# BW1097_Connector.net
KiCad netlist of a schematic drawn in Altium Designer
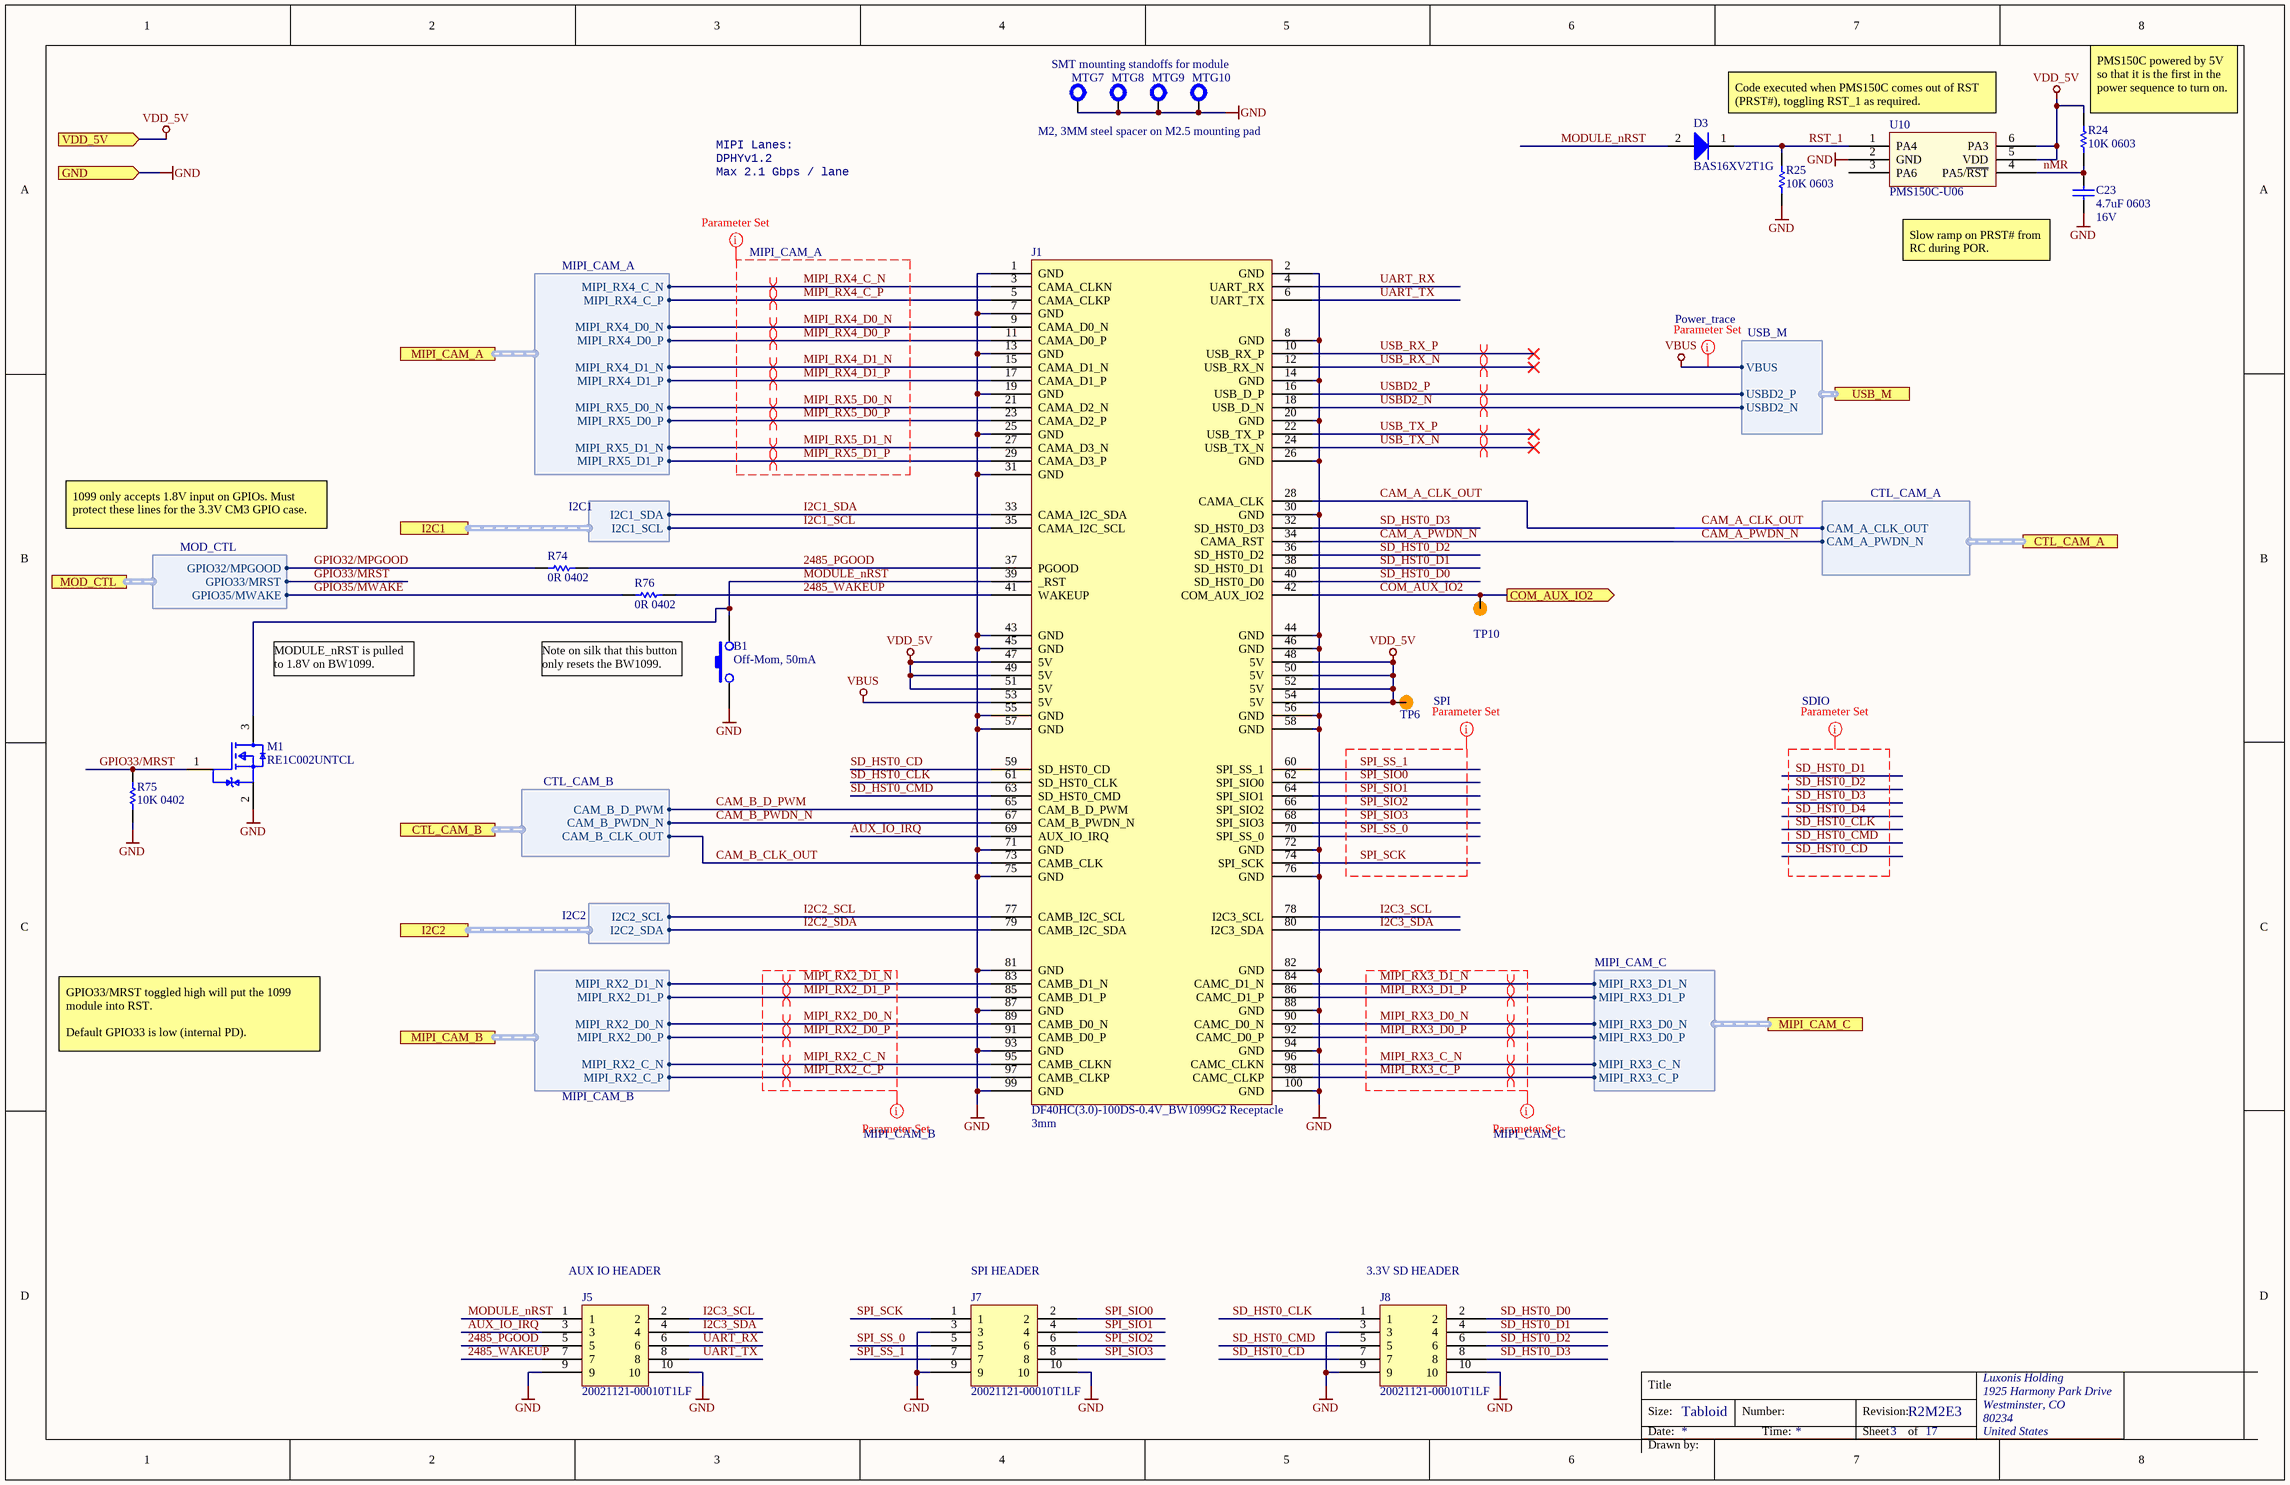
[diagram p0: BW1097_Connector.SchDoc]

(export (version "E")
  (design (tool "Eeschema 10.0.6"))
  (components
    (comp (ref "B1")
      (value "Off-Mom, 50mA")
      (footprint "LuxonisMaster:DTSM-32N-V")
      (description "SWITCH TACTILE SMT 3.5mm * 6mm , brown 160gf")
      (libsource (lib "LuxonisMaster") (part "DTSM-32N-V"))
    )
    (comp (ref "C23")
      (value "4.7uF 0603")
      (footprint "CAP_Altium_Vault_Generic:CAPC0603(1608)100_N")
      (description "CAP CER 4.7UF 16V X5R 0603 10%")
      (fields (field (name "TOLERANCE") "10%") (field (name "VOLTAGE RATING") "16V"))
      (libsource (lib "LuxonisMaster") (part "GRM188R61C475KAAJD"))
    )
    (comp (ref "D3")
      (value "BAS16XV2T1G")
      (footprint "LuxonisMaster:BAS16XV2T1G")
      (description "DIODE GEN PURP 75V 200MA SOD523")
      (libsource (lib "LuxonisMaster") (part "BAS16XV2T1G"))
    )
    (comp (ref "J1")
      (value "DF40HC(3.0)-100DS-0.4V_BW1099G2 Receptacle")
      (footprint "LuxonisMaster:DF40HC-3.0-100DS-0.4V_minpad")
      (description "CONN RCPT 100POS 0.4MM SMD GOLD")
      (fields (field (name "MATED STACKING HEIGHT") "3mm"))
      (libsource (lib "LuxonisMaster") (part "DF40HC(3.0)-100DS-0.4V_BW1099_G2"))
    )
    (comp (ref "J5")
      (value "20021121-00010T1LF")
      (footprint "LuxonisMaster:20021121-00010T1LF")
      (description "CONN HEADER SMD 10POS 1.27MM")
      (libsource (lib "LuxonisMaster") (part "20021121-00010T1LF"))
    )
    (comp (ref "J7")
      (value "20021121-00010T1LF")
      (footprint "LuxonisMaster:20021121-00010T1LF")
      (description "CONN HEADER SMD 10POS 1.27MM")
      (libsource (lib "LuxonisMaster") (part "20021121-00010T1LF"))
    )
    (comp (ref "J8")
      (value "20021121-00010T1LF")
      (footprint "LuxonisMaster:20021121-00010T1LF")
      (description "CONN HEADER SMD 10POS 1.27MM")
      (libsource (lib "LuxonisMaster") (part "20021121-00010T1LF"))
    )
    (comp (ref "M1")
      (value "RE1C002UNTCL")
      (footprint "LuxonisMaster:RE1C002UNTCL")
      (description "MOSFET N-CH 20V 0.2A EMT3")
      (libsource (lib "LuxonisMaster") (part "RE1C002UNTCL"))
    )
    (comp (ref "MTG7")
      (value "M2, 3MM steel spacer on M2.5 mounting pad")
      (footprint "LuxonisMaster:9774030243R")
      (description "MP ROUND STANDOFF M2X0.4 STEEL 3MM")
      (libsource (lib "LuxonisMaster") (part "9774030243R"))
    )
    (comp (ref "MTG8")
      (value "M2, 3MM steel spacer on M2.5 mounting pad")
      (footprint "LuxonisMaster:9774030243R")
      (description "MP ROUND STANDOFF M2X0.4 STEEL 3MM")
      (libsource (lib "LuxonisMaster") (part "9774030243R"))
    )
    (comp (ref "MTG9")
      (value "M2, 3MM steel spacer on M2.5 mounting pad")
      (footprint "LuxonisMaster:9774030243R")
      (description "MP ROUND STANDOFF M2X0.4 STEEL 3MM")
      (libsource (lib "LuxonisMaster") (part "9774030243R"))
    )
    (comp (ref "MTG10")
      (value "M2, 3MM steel spacer on M2.5 mounting pad")
      (footprint "LuxonisMaster:9774030243R")
      (description "MP ROUND STANDOFF M2X0.4 STEEL 3MM")
      (libsource (lib "LuxonisMaster") (part "9774030243R"))
    )
    (comp (ref "R24")
      (value "10K 0603")
      (footprint "RES_Altium_Vault_Generic:RESC0603(1608)_N")
      (description "RES SMD 10K OHM 1% 1/10W 0603")
      (fields (field (name "TOLERANCE") "1%"))
      (libsource (lib "LuxonisMaster") (part "RC0603FR-0710KL"))
    )
    (comp (ref "R25")
      (value "10K 0603")
      (footprint "RES_Altium_Vault_Generic:RESC0603(1608)_N")
      (description "RES SMD 10K OHM 1% 1/10W 0603")
      (fields (field (name "TOLERANCE") "1%"))
      (libsource (lib "LuxonisMaster") (part "RC0603FR-0710KL"))
    )
    (comp (ref "R74")
      (value "0R 0402")
      (footprint "RES_Altium_Vault_Generic:RESC0402(1005)_N")
      (description "RES SMD 0 OHM JUMPER 1/16W 0402")
      (fields (field (name "TOLERANCE") "5%"))
      (libsource (lib "LuxonisMaster") (part "CRCW04020000Z0ED"))
    )
    (comp (ref "R75")
      (value "10K 0402")
      (footprint "RES_Altium_Vault_Generic:RESC0402(1005)_N")
      (fields (field (name "TOLERANCE") "1%"))
      (libsource (lib "LuxonisMaster") (part "RC0402FR-1310KL"))
    )
    (comp (ref "R76")
      (value "0R 0402")
      (footprint "RES_Altium_Vault_Generic:RESC0402(1005)_N")
      (description "RES SMD 0 OHM JUMPER 1/16W 0402")
      (fields (field (name "TOLERANCE") "5%"))
      (libsource (lib "LuxonisMaster") (part "CRCW04020000Z0ED"))
    )
    (comp (ref "TP6")
      (value "TP100_200_NS")
      (footprint "LuxonisMaster:TP100_200_NS")
      (libsource (lib "LuxonisMaster") (part "TEST_POINT"))
    )
    (comp (ref "TP10")
      (value "TP100_200_NS")
      (footprint "LuxonisMaster:TP100_200_NS")
      (libsource (lib "LuxonisMaster") (part "TEST_POINT"))
    )
    (comp (ref "U10")
      (value "PMS150C-U06")
      (footprint "LuxonisMaster:PMS150C-U06")
      (description "Padauk 8bit OTP Type IO Controller - (SOT-23-6)")
      (libsource (lib "LuxonisMaster") (part "PMS150C-U06"))
    )
  )
  (nets
    (net (code "10") (name "/2485_PGOOD") (class "Default")
      (node (ref "J1") (pin "37") (pinfunction "PGOOD_37") (pintype "passive"))
      (node (ref "J5") (pin "5") (pinfunction "5_5") (pintype "passive"))
      (node (ref "R74") (pin "1") (pinfunction "1_1") (pintype "passive"))
    )
    (net (code "11") (name "/2485_WAKEUP") (class "Default")
      (node (ref "J1") (pin "41") (pinfunction "WAKEUP_41") (pintype "passive"))
      (node (ref "J5") (pin "7") (pinfunction "7_7") (pintype "passive"))
      (node (ref "R76") (pin "1") (pinfunction "1_1") (pintype "passive"))
    )
    (net (code "12") (name "/AUX_IO_IRQ") (class "Default")
      (node (ref "J1") (pin "69") (pinfunction "AUX_IO_IRQ_69") (pintype "passive"))
      (node (ref "J5") (pin "3") (pinfunction "3_3") (pintype "passive"))
    )
    (net (code "13") (name "/CAM_A_CLK_OUT") (class "Default")
      (node (ref "J1") (pin "28") (pinfunction "CAMA_CLK_28") (pintype "passive"))
    )
    (net (code "14") (name "/CAM_A_PWDN_N") (class "Default")
      (node (ref "J1") (pin "34") (pinfunction "CAMA_RST_34") (pintype "passive"))
    )
    (net (code "15") (name "/CAM_B_CLK_OUT") (class "Default")
      (node (ref "J1") (pin "73") (pinfunction "CAMB_CLK_73") (pintype "passive"))
    )
    (net (code "16") (name "/CAM_B_D_PWM") (class "Default")
      (node (ref "J1") (pin "65") (pinfunction "CAM_B_D_PWM_65") (pintype "passive"))
    )
    (net (code "17") (name "/CAM_B_PWDN_N") (class "Default")
      (node (ref "J1") (pin "67") (pinfunction "CAM_B_PWDN_N_67") (pintype "passive"))
    )
    (net (code "18") (name "/COM_AUX_IO2") (class "Default")
      (node (ref "J1") (pin "42") (pinfunction "COM_AUX_IO2_42") (pintype "passive"))
      (node (ref "TP10") (pin "1") (pintype "passive"))
    )
    (net (code "19") (name "/GPIO32{slash}MPGOOD") (class "Default")
      (node (ref "R74") (pin "2") (pinfunction "2_2") (pintype "passive"))
    )
    (net (code "20") (name "/GPIO33{slash}MRST") (class "Default")
      (node (ref "M1") (pin "1") (pinfunction "Gate_1") (pintype "passive"))
      (node (ref "R75") (pin "2") (pinfunction "2_2") (pintype "passive"))
    )
    (net (code "21") (name "/GPIO35{slash}MWAKE") (class "Default")
      (node (ref "R76") (pin "2") (pinfunction "2_2") (pintype "passive"))
    )
    (net (code "22") (name "/I2C1_SCL") (class "Default")
      (node (ref "J1") (pin "35") (pinfunction "CAMA_I2C_SCL_35") (pintype "passive"))
    )
    (net (code "23") (name "/I2C1_SDA") (class "Default")
      (node (ref "J1") (pin "33") (pinfunction "CAMA_I2C_SDA_33") (pintype "passive"))
    )
    (net (code "24") (name "/I2C2_SCL") (class "Default")
      (node (ref "J1") (pin "77") (pinfunction "CAMB_I2C_SCL_77") (pintype "passive"))
    )
    (net (code "25") (name "/I2C2_SDA") (class "Default")
      (node (ref "J1") (pin "79") (pinfunction "CAMB_I2C_SDA_79") (pintype "passive"))
    )
    (net (code "26") (name "/I2C3_SCL") (class "Default")
      (node (ref "J1") (pin "78") (pinfunction "I2C3_SCL_78") (pintype "passive"))
      (node (ref "J5") (pin "2") (pinfunction "2_2") (pintype "passive"))
    )
    (net (code "27") (name "/I2C3_SDA") (class "Default")
      (node (ref "J1") (pin "80") (pinfunction "I2C3_SDA_80") (pintype "passive"))
      (node (ref "J5") (pin "4") (pinfunction "4_4") (pintype "passive"))
    )
    (net (code "28") (name "/MIPI_RX2_C_N") (class "Default")
      (node (ref "J1") (pin "95") (pinfunction "CAMB_CLKN_95") (pintype "passive"))
    )
    (net (code "29") (name "/MIPI_RX2_C_P") (class "Default")
      (node (ref "J1") (pin "97") (pinfunction "CAMB_CLKP_97") (pintype "passive"))
    )
    (net (code "30") (name "/MIPI_RX2_D0_N") (class "Default")
      (node (ref "J1") (pin "89") (pinfunction "CAMB_D0_N_89") (pintype "passive"))
    )
    (net (code "31") (name "/MIPI_RX2_D0_P") (class "Default")
      (node (ref "J1") (pin "91") (pinfunction "CAMB_D0_P_91") (pintype "passive"))
    )
    (net (code "32") (name "/MIPI_RX2_D1_N") (class "Default")
      (node (ref "J1") (pin "83") (pinfunction "CAMB_D1_N_83") (pintype "passive"))
    )
    (net (code "33") (name "/MIPI_RX2_D1_P") (class "Default")
      (node (ref "J1") (pin "85") (pinfunction "CAMB_D1_P_85") (pintype "passive"))
    )
    (net (code "34") (name "/MIPI_RX3_C_N") (class "Default")
      (node (ref "J1") (pin "96") (pinfunction "CAMC_CLKN_96") (pintype "passive"))
    )
    (net (code "35") (name "/MIPI_RX3_C_P") (class "Default")
      (node (ref "J1") (pin "98") (pinfunction "CAMC_CLKP_98") (pintype "passive"))
    )
    (net (code "36") (name "/MIPI_RX3_D0_N") (class "Default")
      (node (ref "J1") (pin "90") (pinfunction "CAMC_D0_N_90") (pintype "passive"))
    )
    (net (code "37") (name "/MIPI_RX3_D0_P") (class "Default")
      (node (ref "J1") (pin "92") (pinfunction "CAMC_D0_P_92") (pintype "passive"))
    )
    (net (code "38") (name "/MIPI_RX3_D1_N") (class "Default")
      (node (ref "J1") (pin "84") (pinfunction "CAMC_D1_N_84") (pintype "passive"))
    )
    (net (code "39") (name "/MIPI_RX3_D1_P") (class "Default")
      (node (ref "J1") (pin "86") (pinfunction "CAMC_D1_P_86") (pintype "passive"))
    )
    (net (code "40") (name "/MIPI_RX4_C_N") (class "Default")
      (node (ref "J1") (pin "3") (pinfunction "CAMA_CLKN_3") (pintype "passive"))
    )
    (net (code "41") (name "/MIPI_RX4_C_P") (class "Default")
      (node (ref "J1") (pin "5") (pinfunction "CAMA_CLKP_5") (pintype "passive"))
    )
    (net (code "42") (name "/MIPI_RX4_D0_N") (class "Default")
      (node (ref "J1") (pin "9") (pinfunction "CAMA_D0_N_9") (pintype "passive"))
    )
    (net (code "43") (name "/MIPI_RX4_D0_P") (class "Default")
      (node (ref "J1") (pin "11") (pinfunction "CAMA_D0_P_11") (pintype "passive"))
    )
    (net (code "44") (name "/MIPI_RX4_D1_N") (class "Default")
      (node (ref "J1") (pin "15") (pinfunction "CAMA_D1_N_15") (pintype "passive"))
    )
    (net (code "45") (name "/MIPI_RX4_D1_P") (class "Default")
      (node (ref "J1") (pin "17") (pinfunction "CAMA_D1_P_17") (pintype "passive"))
    )
    (net (code "46") (name "/MIPI_RX5_D0_N") (class "Default")
      (node (ref "J1") (pin "21") (pinfunction "CAMA_D2_N_21") (pintype "passive"))
    )
    (net (code "47") (name "/MIPI_RX5_D0_P") (class "Default")
      (node (ref "J1") (pin "23") (pinfunction "CAMA_D2_P_23") (pintype "passive"))
    )
    (net (code "48") (name "/MIPI_RX5_D1_N") (class "Default")
      (node (ref "J1") (pin "27") (pinfunction "CAMA_D3_N_27") (pintype "passive"))
    )
    (net (code "49") (name "/MIPI_RX5_D1_P") (class "Default")
      (node (ref "J1") (pin "29") (pinfunction "CAMA_D3_P_29") (pintype "passive"))
    )
    (net (code "50") (name "/MODULE_nRST") (class "Default")
      (node (ref "B1") (pin "2") (pinfunction "2_2") (pintype "passive"))
      (node (ref "D3") (pin "2") (pinfunction "A_2") (pintype "passive"))
      (node (ref "J1") (pin "39") (pinfunction "_RST_39") (pintype "passive"))
      (node (ref "J5") (pin "1") (pinfunction "1_1") (pintype "passive"))
      (node (ref "M1") (pin "3") (pinfunction "Drain_3") (pintype "passive"))
    )
    (net (code "51") (name "/RST_1") (class "Default")
      (node (ref "D3") (pin "1") (pinfunction "K_1") (pintype "passive"))
      (node (ref "R25") (pin "2") (pinfunction "2_2") (pintype "passive"))
      (node (ref "U10") (pin "1") (pinfunction "PA4_1") (pintype "passive"))
    )
    (net (code "52") (name "/SD_HST0_CD") (class "Default")
      (node (ref "J1") (pin "59") (pinfunction "SD_HST0_CD_59") (pintype "passive"))
      (node (ref "J8") (pin "7") (pinfunction "7_7") (pintype "passive"))
    )
    (net (code "53") (name "/SD_HST0_CLK") (class "Default")
      (node (ref "J1") (pin "61") (pinfunction "SD_HST0_CLK_61") (pintype "passive"))
      (node (ref "J8") (pin "1") (pinfunction "1_1") (pintype "passive"))
    )
    (net (code "54") (name "/SD_HST0_CMD") (class "Default")
      (node (ref "J1") (pin "63") (pinfunction "SD_HST0_CMD_63") (pintype "passive"))
      (node (ref "J8") (pin "5") (pinfunction "5_5") (pintype "passive"))
    )
    (net (code "55") (name "/SD_HST0_D0") (class "Default")
      (node (ref "J1") (pin "40") (pinfunction "SD_HST0_D0_40") (pintype "passive"))
      (node (ref "J8") (pin "2") (pinfunction "2_2") (pintype "passive"))
    )
    (net (code "56") (name "/SD_HST0_D1") (class "Default")
      (node (ref "J1") (pin "38") (pinfunction "SD_HST0_D1_38") (pintype "passive"))
      (node (ref "J8") (pin "4") (pinfunction "4_4") (pintype "passive"))
    )
    (net (code "57") (name "/SD_HST0_D2") (class "Default")
      (node (ref "J1") (pin "36") (pinfunction "SD_HST0_D2_36") (pintype "passive"))
      (node (ref "J8") (pin "6") (pinfunction "6_6") (pintype "passive"))
    )
    (net (code "58") (name "/SD_HST0_D3") (class "Default")
      (node (ref "J1") (pin "32") (pinfunction "SD_HST0_D3_32") (pintype "passive"))
      (node (ref "J8") (pin "8") (pinfunction "8_8") (pintype "passive"))
    )
    (net (code "60") (name "/SPI_SCK") (class "Default")
      (node (ref "J1") (pin "74") (pinfunction "SPI_SCK_74") (pintype "passive"))
      (node (ref "J7") (pin "1") (pinfunction "1_1") (pintype "passive"))
    )
    (net (code "61") (name "/SPI_SIO0") (class "Default")
      (node (ref "J1") (pin "62") (pinfunction "SPI_SIO0_62") (pintype "passive"))
      (node (ref "J7") (pin "2") (pinfunction "2_2") (pintype "passive"))
    )
    (net (code "62") (name "/SPI_SIO1") (class "Default")
      (node (ref "J1") (pin "64") (pinfunction "SPI_SIO1_64") (pintype "passive"))
      (node (ref "J7") (pin "4") (pinfunction "4_4") (pintype "passive"))
    )
    (net (code "63") (name "/SPI_SIO2") (class "Default")
      (node (ref "J1") (pin "66") (pinfunction "SPI_SIO2_66") (pintype "passive"))
      (node (ref "J7") (pin "6") (pinfunction "6_6") (pintype "passive"))
    )
    (net (code "64") (name "/SPI_SIO3") (class "Default")
      (node (ref "J1") (pin "68") (pinfunction "SPI_SIO3_68") (pintype "passive"))
      (node (ref "J7") (pin "8") (pinfunction "8_8") (pintype "passive"))
    )
    (net (code "65") (name "/SPI_SS_0") (class "Default")
      (node (ref "J1") (pin "70") (pinfunction "SPI_SS_0_70") (pintype "passive"))
      (node (ref "J7") (pin "5") (pinfunction "5_5") (pintype "passive"))
    )
    (net (code "66") (name "/SPI_SS_1") (class "Default")
      (node (ref "J1") (pin "60") (pinfunction "SPI_SS_1_60") (pintype "passive"))
      (node (ref "J7") (pin "7") (pinfunction "7_7") (pintype "passive"))
    )
    (net (code "67") (name "/UART_RX") (class "Default")
      (node (ref "J1") (pin "4") (pinfunction "UART_RX_4") (pintype "passive"))
      (node (ref "J5") (pin "6") (pinfunction "6_6") (pintype "passive"))
    )
    (net (code "68") (name "/UART_TX") (class "Default")
      (node (ref "J1") (pin "6") (pinfunction "UART_TX_6") (pintype "passive"))
      (node (ref "J5") (pin "8") (pinfunction "8_8") (pintype "passive"))
    )
    (net (code "69") (name "/USBD2_N") (class "Default")
      (node (ref "J1") (pin "18") (pinfunction "USB_D_N_18") (pintype "passive"))
    )
    (net (code "70") (name "/USBD2_P") (class "Default")
      (node (ref "J1") (pin "16") (pinfunction "USB_D_P_16") (pintype "passive"))
    )
    (net (code "71") (name "/USB_RX_N") (class "Default")
      (node (ref "J1") (pin "12") (pinfunction "USB_RX_N_12") (pintype "passive+no_connect"))
    )
    (net (code "72") (name "/USB_RX_P") (class "Default")
      (node (ref "J1") (pin "10") (pinfunction "USB_RX_P_10") (pintype "passive+no_connect"))
    )
    (net (code "73") (name "/USB_TX_N") (class "Default")
      (node (ref "J1") (pin "24") (pinfunction "USB_TX_N_24") (pintype "passive+no_connect"))
    )
    (net (code "74") (name "/USB_TX_P") (class "Default")
      (node (ref "J1") (pin "22") (pinfunction "USB_TX_P_22") (pintype "passive+no_connect"))
    )
    (net (code "75") (name "/nMR") (class "Default")
      (node (ref "C23") (pin "2") (pinfunction "2_2") (pintype "passive"))
      (node (ref "R24") (pin "1") (pinfunction "1_1") (pintype "passive"))
      (node (ref "U10") (pin "4") (pinfunction "PA5/~{RST}_4") (pintype "passive"))
    )
    (net (code "85") (name "GND") (class "Default")
      (node (ref "B1") (pin "1") (pinfunction "1_1") (pintype "passive"))
      (node (ref "C23") (pin "1") (pinfunction "1_1") (pintype "passive"))
      (node (ref "J1") (pin "1") (pinfunction "GND_1") (pintype "passive"))
      (node (ref "J1") (pin "100") (pinfunction "GND_100") (pintype "passive"))
      (node (ref "J1") (pin "13") (pinfunction "GND_13") (pintype "passive"))
      (node (ref "J1") (pin "14") (pinfunction "GND_14") (pintype "passive"))
      (node (ref "J1") (pin "19") (pinfunction "GND_19") (pintype "passive"))
      (node (ref "J1") (pin "2") (pinfunction "GND_2") (pintype "passive"))
      (node (ref "J1") (pin "20") (pinfunction "GND_20") (pintype "passive"))
      (node (ref "J1") (pin "25") (pinfunction "GND_25") (pintype "passive"))
      (node (ref "J1") (pin "26") (pinfunction "GND_26") (pintype "passive"))
      (node (ref "J1") (pin "30") (pinfunction "GND_30") (pintype "passive"))
      (node (ref "J1") (pin "31") (pinfunction "GND_31") (pintype "passive"))
      (node (ref "J1") (pin "43") (pinfunction "GND_43") (pintype "passive"))
      (node (ref "J1") (pin "44") (pinfunction "GND_44") (pintype "passive"))
      (node (ref "J1") (pin "45") (pinfunction "GND_45") (pintype "passive"))
      (node (ref "J1") (pin "46") (pinfunction "GND_46") (pintype "passive"))
      (node (ref "J1") (pin "55") (pinfunction "GND_55") (pintype "passive"))
      (node (ref "J1") (pin "56") (pinfunction "GND_56") (pintype "passive"))
      (node (ref "J1") (pin "57") (pinfunction "GND_57") (pintype "passive"))
      (node (ref "J1") (pin "58") (pinfunction "GND_58") (pintype "passive"))
      (node (ref "J1") (pin "7") (pinfunction "GND_7") (pintype "passive"))
      (node (ref "J1") (pin "71") (pinfunction "GND_71") (pintype "passive"))
      (node (ref "J1") (pin "72") (pinfunction "GND_72") (pintype "passive"))
      (node (ref "J1") (pin "75") (pinfunction "GND_75") (pintype "passive"))
      (node (ref "J1") (pin "76") (pinfunction "GND_76") (pintype "passive"))
      (node (ref "J1") (pin "8") (pinfunction "GND_8") (pintype "passive"))
      (node (ref "J1") (pin "81") (pinfunction "GND_81") (pintype "passive"))
      (node (ref "J1") (pin "82") (pinfunction "GND_82") (pintype "passive"))
      (node (ref "J1") (pin "87") (pinfunction "GND_87") (pintype "passive"))
      (node (ref "J1") (pin "88") (pinfunction "GND_88") (pintype "passive"))
      (node (ref "J1") (pin "93") (pinfunction "GND_93") (pintype "passive"))
      (node (ref "J1") (pin "94") (pinfunction "GND_94") (pintype "passive"))
      (node (ref "J1") (pin "99") (pinfunction "GND_99") (pintype "passive"))
      (node (ref "J5") (pin "10") (pinfunction "10_10") (pintype "passive"))
      (node (ref "J5") (pin "9") (pinfunction "9_9") (pintype "passive"))
      (node (ref "J7") (pin "10") (pinfunction "10_10") (pintype "passive"))
      (node (ref "J7") (pin "3") (pinfunction "3_3") (pintype "passive"))
      (node (ref "J7") (pin "9") (pinfunction "9_9") (pintype "passive"))
      (node (ref "J8") (pin "10") (pinfunction "10_10") (pintype "passive"))
      (node (ref "J8") (pin "3") (pinfunction "3_3") (pintype "passive"))
      (node (ref "J8") (pin "9") (pinfunction "9_9") (pintype "passive"))
      (node (ref "M1") (pin "2") (pinfunction "Source_2") (pintype "passive"))
      (node (ref "MTG10") (pin "1") (pintype "passive"))
      (node (ref "MTG7") (pin "1") (pintype "passive"))
      (node (ref "MTG8") (pin "1") (pintype "passive"))
      (node (ref "MTG9") (pin "1") (pintype "passive"))
      (node (ref "R25") (pin "1") (pinfunction "1_1") (pintype "passive"))
      (node (ref "R75") (pin "1") (pinfunction "1_1") (pintype "passive"))
      (node (ref "U10") (pin "2") (pinfunction "GND_2") (pintype "passive"))
    )
    (net (code "86") (name "VBUS") (class "Default")
      (node (ref "J1") (pin "53") (pinfunction "5V_53") (pintype "passive"))
    )
    (net (code "87") (name "VDD_5V") (class "Default")
      (node (ref "J1") (pin "47") (pinfunction "5V_47") (pintype "passive"))
      (node (ref "J1") (pin "48") (pinfunction "5V_48") (pintype "passive"))
      (node (ref "J1") (pin "49") (pinfunction "5V_49") (pintype "passive"))
      (node (ref "J1") (pin "50") (pinfunction "5V_50") (pintype "passive"))
      (node (ref "J1") (pin "51") (pinfunction "5V_51") (pintype "passive"))
      (node (ref "J1") (pin "52") (pinfunction "5V_52") (pintype "passive"))
      (node (ref "J1") (pin "54") (pinfunction "5V_54") (pintype "passive"))
      (node (ref "R24") (pin "2") (pinfunction "2_2") (pintype "passive"))
      (node (ref "TP6") (pin "1") (pintype "passive"))
      (node (ref "U10") (pin "5") (pinfunction "VDD_5") (pintype "passive"))
      (node (ref "U10") (pin "6") (pinfunction "PA3_6") (pintype "passive"))
    )
    (net (code "88") (name "unconnected-(U10-PA6-Pad3)") (class "Default")
      (node (ref "U10") (pin "3") (pinfunction "PA6_3") (pintype "passive"))
    )
  )
)
